# bappr_easyeda_file_source.net
KiCad netlist of a schematic drawn in EasyEDA
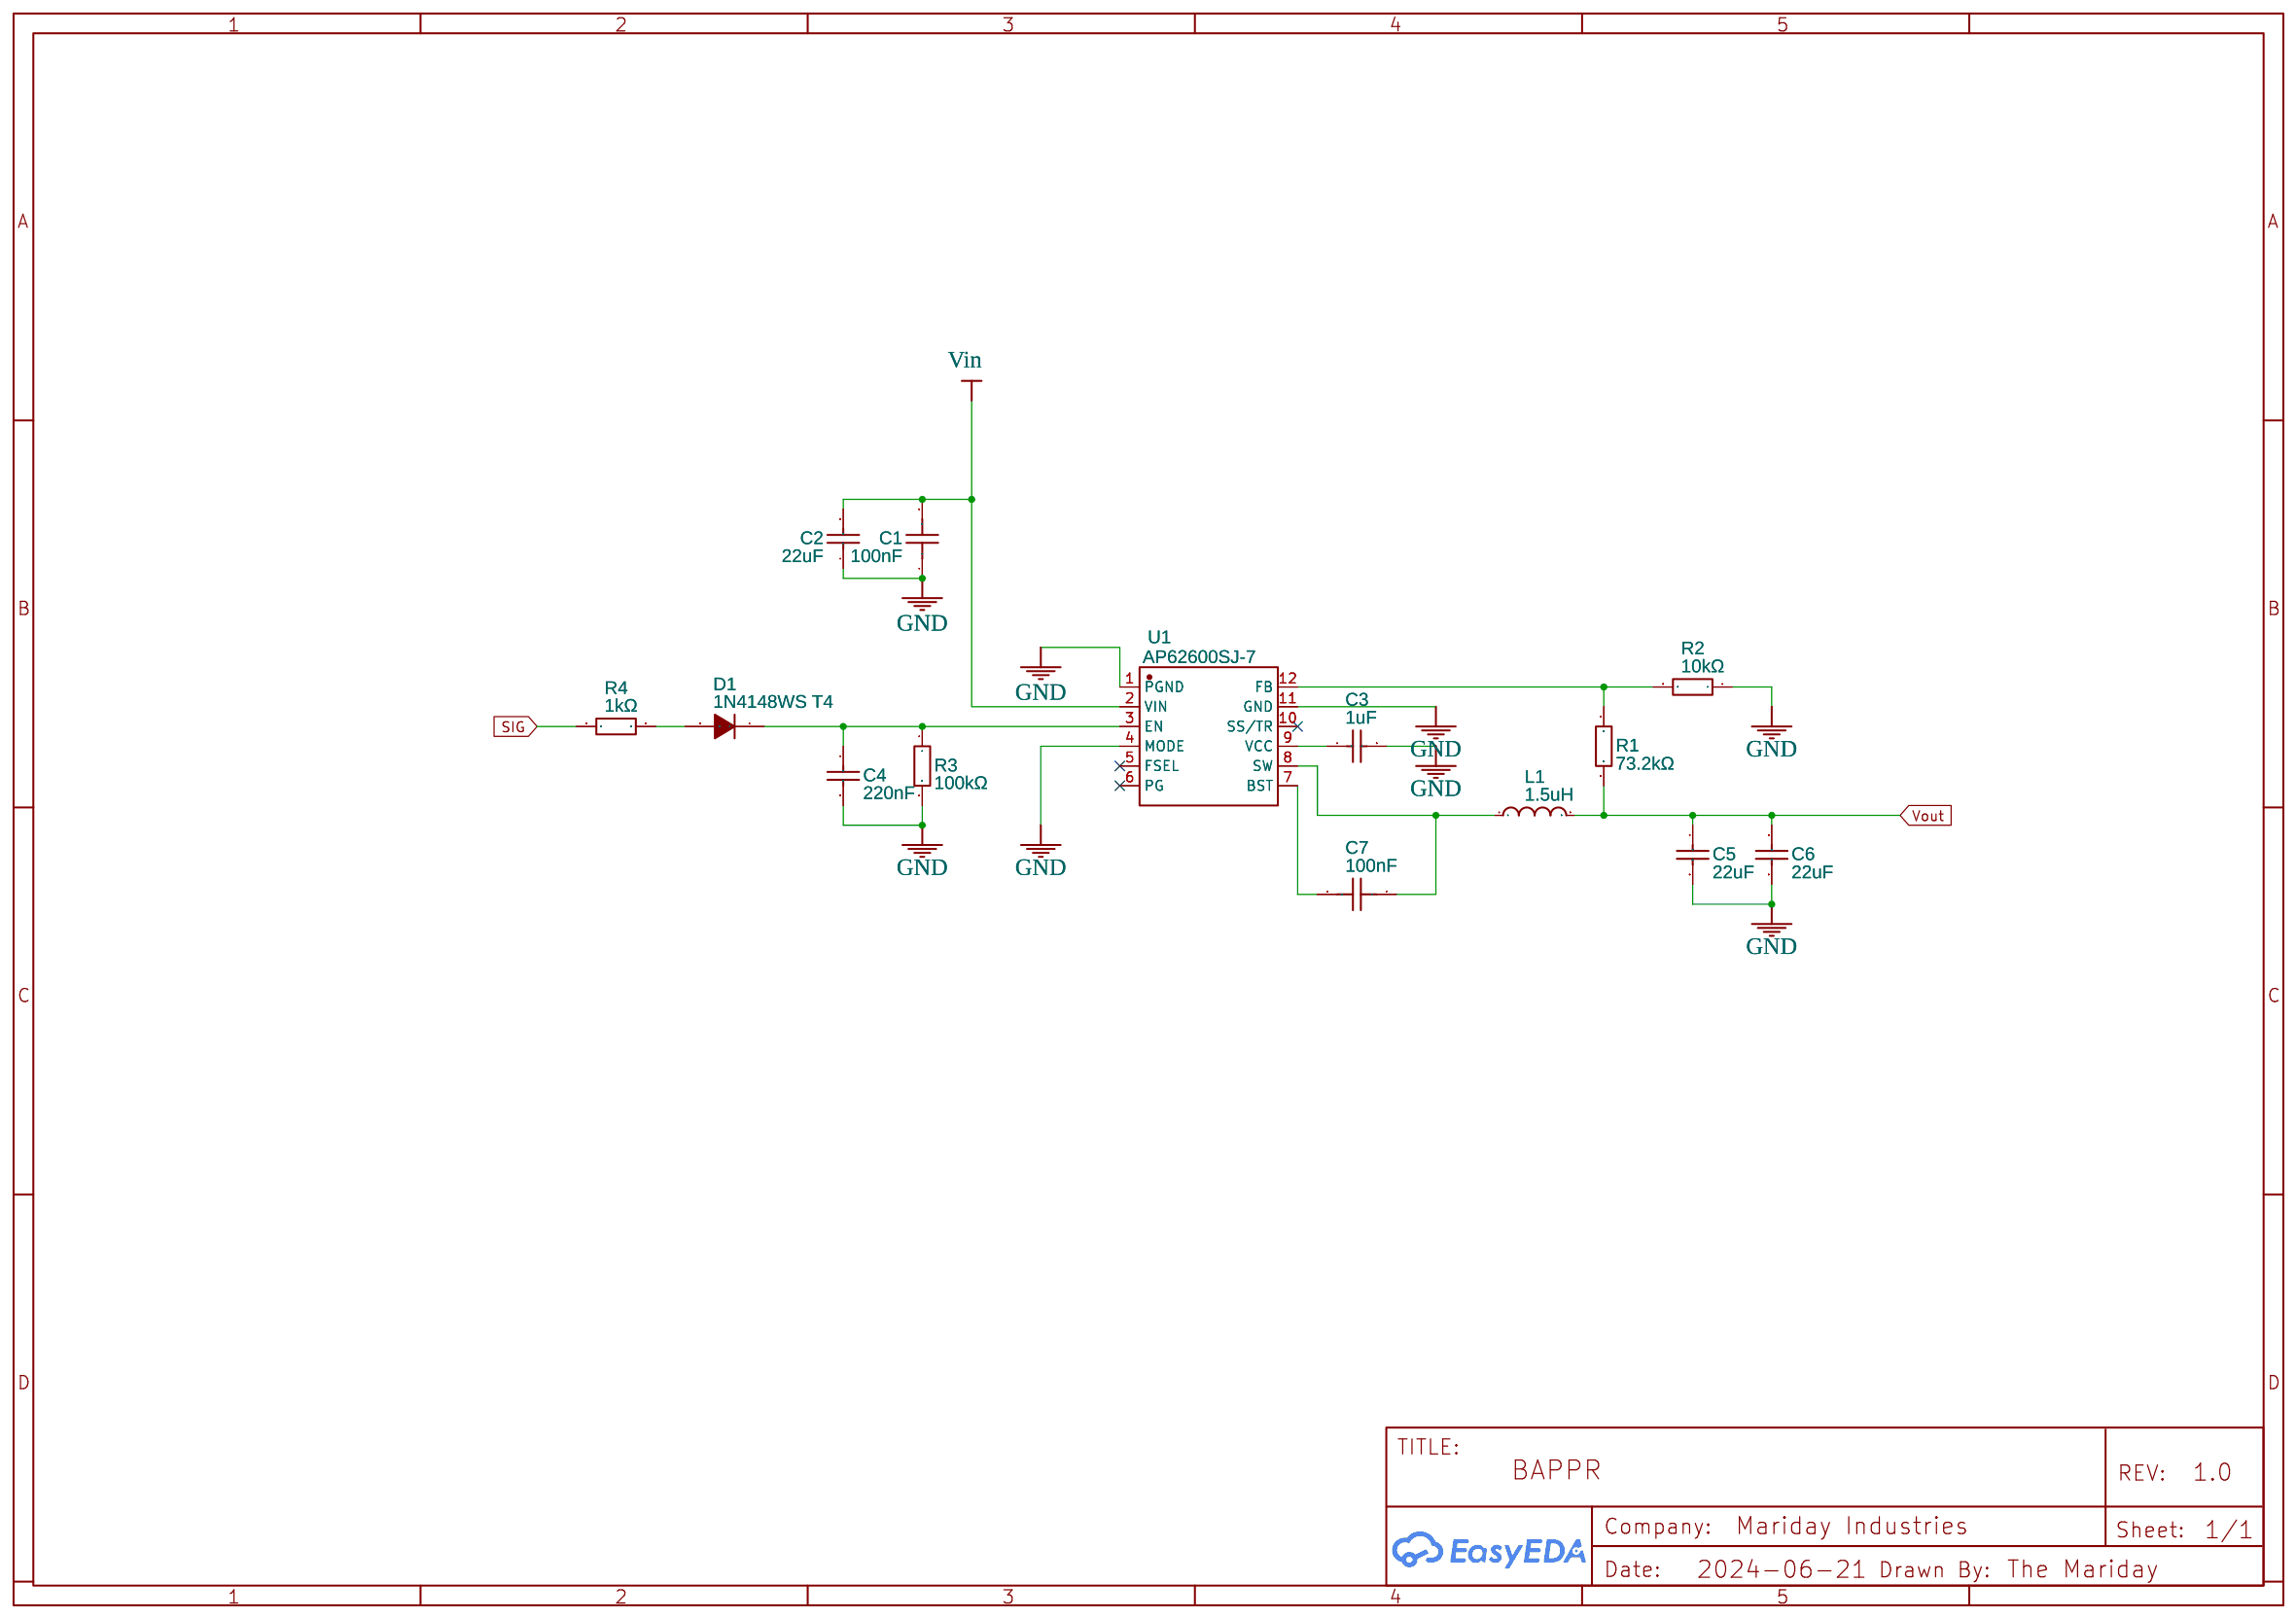
[diagram p0: schematic sheet]

(export (version "E")
  (design (tool "Eeschema 10.0.6"))
  (components
    (comp (ref "C1")
      (value "100nF")
      (fields
        (field (name "Manufacturer Part") "CC0603KRX7R9BB104")
        (field (name "Manufacturer") "YAGEO(国巨)")
      )
      (libsource (lib "") (part "CC0603KRX7R9BB104_1"))
    )
    (comp (ref "C2")
      (value "22uF")
      (fields
        (field (name "Manufacturer Part") "CL31A226KAHNNNE")
        (field (name "Manufacturer") "SAMSUNG(三星)")
      )
      (libsource (lib "") (part "CL31A226KAHNNNE"))
    )
    (comp (ref "C3")
      (value "1uF")
      (fields
        (field (name "Manufacturer Part") "CL10A105KB8NNNC")
        (field (name "Manufacturer") "SAMSUNG(三星)")
      )
      (libsource (lib "") (part "CL10A105KB8NNNC"))
    )
    (comp (ref "C4")
      (value "220nF")
      (fields
        (field (name "Manufacturer Part") "CL10B224KA8NNNC")
        (field (name "Manufacturer") "SAMSUNG(三星)")
      )
      (libsource (lib "") (part "CL10B224KA8NNNC"))
    )
    (comp (ref "C5")
      (value "22uF")
      (fields
        (field (name "Manufacturer Part") "CL31A226KAHNNNE")
        (field (name "Manufacturer") "SAMSUNG(三星)")
      )
      (libsource (lib "") (part "CL31A226KAHNNNE_1"))
    )
    (comp (ref "C6")
      (value "22uF")
      (fields
        (field (name "Manufacturer Part") "CL31A226KAHNNNE")
        (field (name "Manufacturer") "SAMSUNG(三星)")
      )
      (libsource (lib "") (part "CL31A226KAHNNNE_1"))
    )
    (comp (ref "C7")
      (value "100nF")
      (fields
        (field (name "Manufacturer Part") "CC0603KRX7R9BB104")
        (field (name "Manufacturer") "YAGEO(国巨)")
      )
      (libsource (lib "") (part "CC0603KRX7R9BB104"))
    )
    (comp (ref "D1")
      (value "1N4148WS T4")
      (fields (field (name "Manufacturer Part") "1N4148WS") (field (name "Manufacturer") "CJ(江苏长电/长晶)"))
      (libsource (lib "") (part "1N4148WS T4"))
    )
    (comp (ref "L1")
      (value "1.5uH")
      (fields
        (field (name "Manufacturer Part") "IHLP2525CZER1R5M01")
        (field (name "Manufacturer") "VISHAY(威世)")
      )
      (libsource (lib "") (part "IHLP2525CZER1R5M01"))
    )
    (comp (ref "R1")
      (value "73.2kΩ")
      (fields
        (field (name "Manufacturer Part") "0603WAF7322T5E")
        (field (name "Manufacturer") "UNI-ROYAL(厚声)")
      )
      (libsource (lib "") (part "0603WAF7322T5E"))
    )
    (comp (ref "R2")
      (value "10kΩ")
      (fields
        (field (name "Manufacturer Part") "0603WAF1002T5E")
        (field (name "Manufacturer") "UNI-ROYAL(厚声)")
      )
      (libsource (lib "") (part "0603WAF1002T5E"))
    )
    (comp (ref "R3")
      (value "100kΩ")
      (fields
        (field (name "Manufacturer Part") "0603WAF1003T5E")
        (field (name "Manufacturer") "UNI-ROYAL(厚声)")
      )
      (libsource (lib "") (part "0603WAF1003T5E"))
    )
    (comp (ref "R4")
      (value "1kΩ")
      (fields
        (field (name "Manufacturer Part") "0603WAF1001T5E")
        (field (name "Manufacturer") "UNI-ROYAL(厚声)")
      )
      (libsource (lib "") (part "0603WAF1001T5E"))
    )
    (comp (ref "U1")
      (value "AP62600SJ-7")
      (fields (field (name "Manufacturer") "DIODES(美台)"))
      (libsource (lib "") (part "AP62600SJ-7"))
    )
  )
  (nets
    (net (code "1") (name "GND") (class "Default")
      (node (ref "C1") (pin "1") (pinfunction "1_1") (pintype "unspecified"))
      (node (ref "C2") (pin "1") (pinfunction "1_1") (pintype "input"))
      (node (ref "C3") (pin "2") (pinfunction "2_2") (pintype "input"))
      (node (ref "C4") (pin "2") (pinfunction "2_2") (pintype "input"))
      (node (ref "C5") (pin "2") (pinfunction "2_2") (pintype "input"))
      (node (ref "C6") (pin "2") (pinfunction "2_2") (pintype "input"))
      (node (ref "R2") (pin "1") (pinfunction "1_1") (pintype "input"))
      (node (ref "R3") (pin "2") (pinfunction "2_2") (pintype "input"))
      (node (ref "U1") (pin "1") (pinfunction "PGND_1") (pintype "unspecified"))
      (node (ref "U1") (pin "11") (pinfunction "GND_11") (pintype "unspecified"))
      (node (ref "U1") (pin "4") (pinfunction "MODE_4") (pintype "unspecified"))
    )
    (net (code "2") (name "Net-(D1-A)") (class "Default")
      (node (ref "D1") (pin "2") (pinfunction "A_2") (pintype "unspecified"))
      (node (ref "R4") (pin "2") (pinfunction "2_2") (pintype "input"))
    )
    (net (code "3") (name "Net-(D1-K)") (class "Default")
      (node (ref "C4") (pin "1") (pinfunction "1_1") (pintype "input"))
      (node (ref "D1") (pin "1") (pinfunction "K_1") (pintype "unspecified"))
      (node (ref "R3") (pin "1") (pinfunction "1_1") (pintype "input"))
      (node (ref "U1") (pin "3") (pinfunction "EN_3") (pintype "unspecified"))
    )
    (net (code "4") (name "Net-(U1-BST)") (class "Default")
      (node (ref "C7") (pin "2") (pinfunction "2_2") (pintype "unspecified"))
      (node (ref "U1") (pin "7") (pinfunction "BST_7") (pintype "unspecified"))
    )
    (net (code "5") (name "Net-(U1-FB)") (class "Default")
      (node (ref "R1") (pin "1") (pinfunction "1_1") (pintype "input"))
      (node (ref "R2") (pin "2") (pinfunction "2_2") (pintype "input"))
      (node (ref "U1") (pin "12") (pinfunction "FB_12") (pintype "unspecified"))
    )
    (net (code "6") (name "Net-(U1-SW)") (class "Default")
      (node (ref "C7") (pin "1") (pinfunction "1_1") (pintype "unspecified"))
      (node (ref "L1") (pin "1") (pinfunction "1_1") (pintype "unspecified"))
      (node (ref "U1") (pin "8") (pinfunction "SW_8") (pintype "unspecified"))
    )
    (net (code "7") (name "Net-(U1-VCC)") (class "Default")
      (node (ref "C3") (pin "1") (pinfunction "1_1") (pintype "input"))
      (node (ref "U1") (pin "9") (pinfunction "VCC_9") (pintype "unspecified"))
    )
    (net (code "8") (name "SIG") (class "Default")
      (node (ref "R4") (pin "1") (pinfunction "1_1") (pintype "input"))
    )
    (net (code "9") (name "Vin") (class "Default")
      (node (ref "C1") (pin "2") (pinfunction "2_2") (pintype "unspecified"))
      (node (ref "C2") (pin "2") (pinfunction "2_2") (pintype "input"))
      (node (ref "U1") (pin "2") (pinfunction "VIN_2") (pintype "unspecified"))
    )
    (net (code "10") (name "Vout") (class "Default")
      (node (ref "C5") (pin "1") (pinfunction "1_1") (pintype "input"))
      (node (ref "C6") (pin "1") (pinfunction "1_1") (pintype "input"))
      (node (ref "L1") (pin "2") (pinfunction "2_2") (pintype "unspecified"))
      (node (ref "R1") (pin "2") (pinfunction "2_2") (pintype "input"))
    )
    (net (code "11") (name "unconnected-(U1-FSEL-Pad5)") (class "Default")
      (node (ref "U1") (pin "5") (pinfunction "FSEL_5") (pintype "unspecified+no_connect"))
    )
    (net (code "12") (name "unconnected-(U1-PG-Pad6)") (class "Default")
      (node (ref "U1") (pin "6") (pinfunction "PG_6") (pintype "unspecified+no_connect"))
    )
    (net (code "13") (name "unconnected-(U1-SS{slash}TR-Pad10)") (class "Default")
      (node (ref "U1") (pin "10") (pinfunction "SS/TR_10") (pintype "unspecified+no_connect"))
    )
  )
)
